# untitled.net
KiCad netlist of a schematic drawn in EAGLE
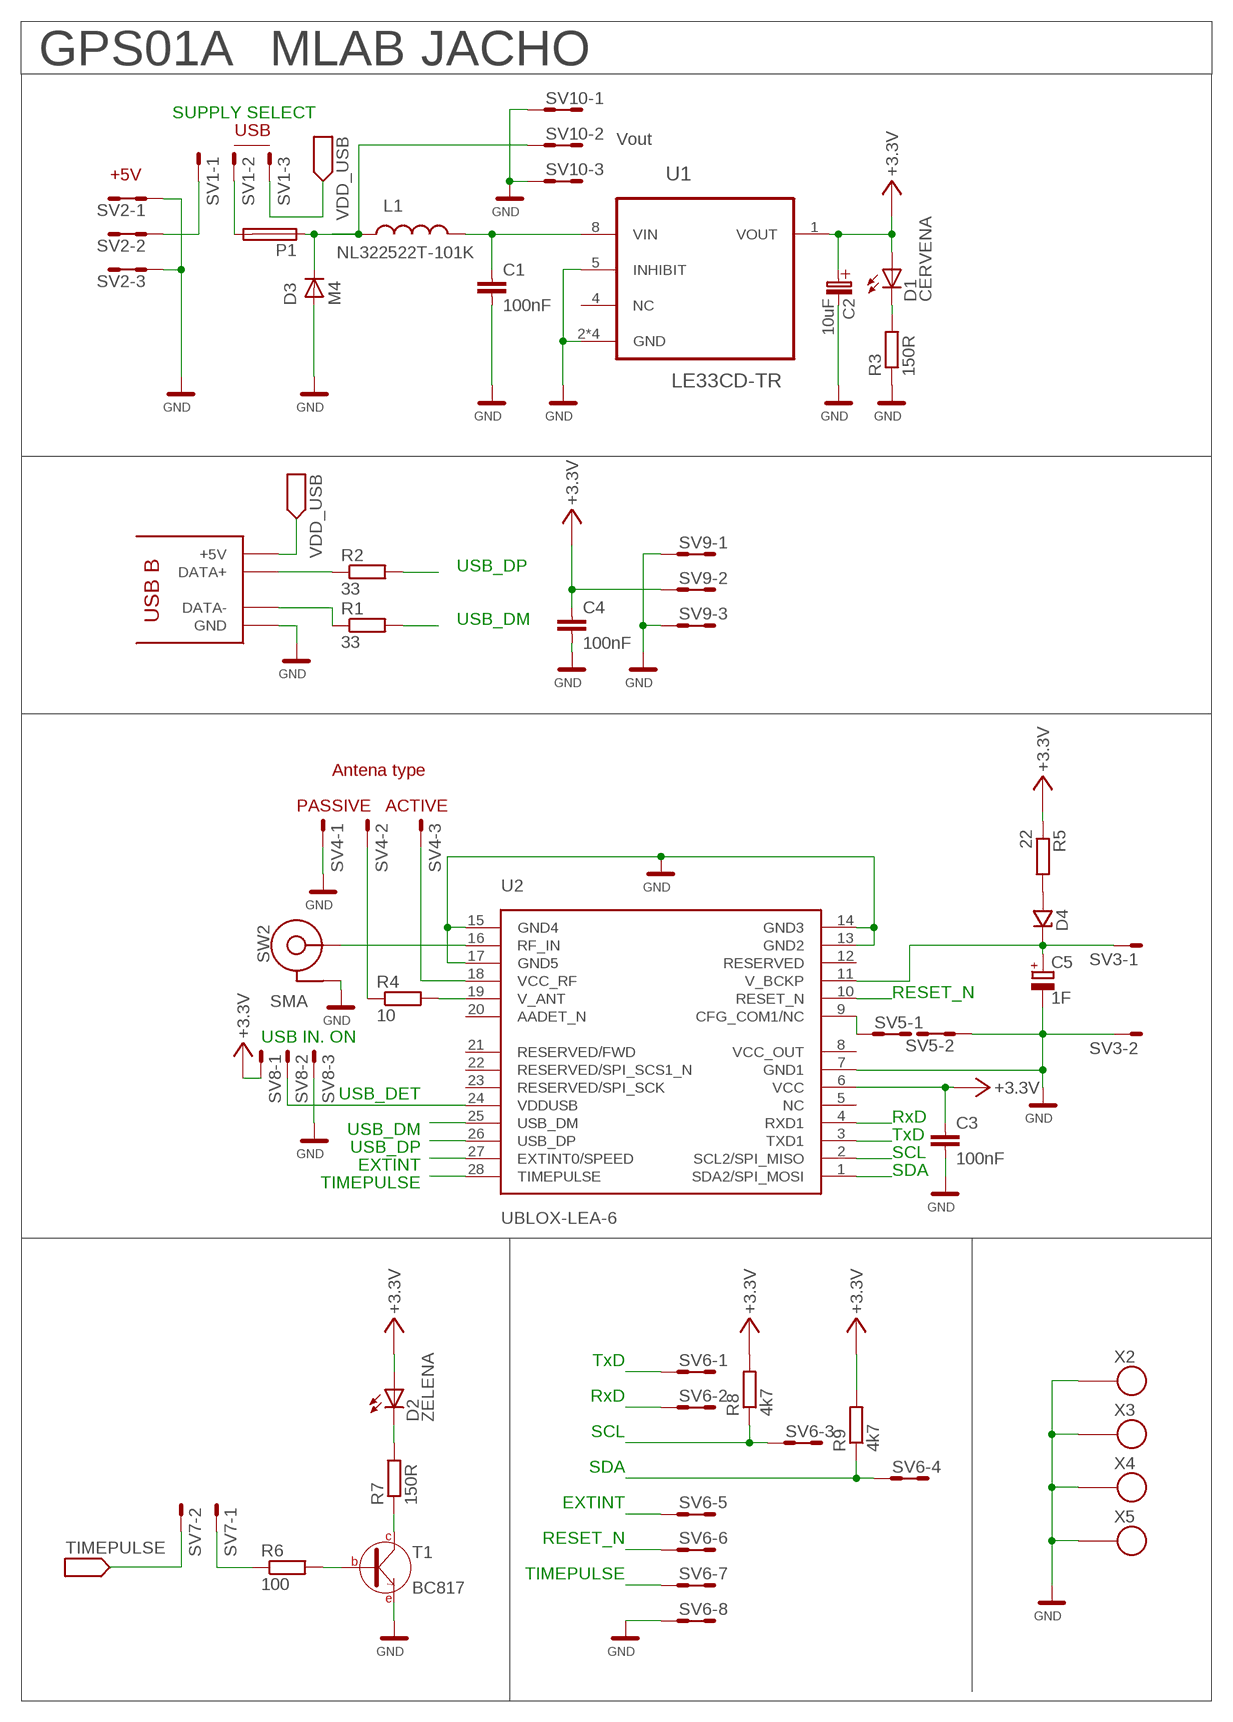
[diagram p0: schematic, sheet 1]

(export (version "E")
  (design (tool "Eeschema 10.0.6"))
  (components
    (comp (ref "C1")
      (value "100nF")
      (footprint "eagle-import:C0805")
      (libsource (lib "eagle-import") (part "C0805"))
    )
    (comp (ref "C2") (value "10uF") (footprint "eagle-import:B") (libsource (lib "eagle-import") (part "B")))
    (comp (ref "C3")
      (value "100nF")
      (footprint "eagle-import:C0805")
      (libsource (lib "eagle-import") (part "C0805"))
    )
    (comp (ref "C4")
      (value "100nF")
      (footprint "eagle-import:C0805")
      (libsource (lib "eagle-import") (part "C0805"))
    )
    (comp (ref "C5")
      (value "1F")
      (footprint "eagle-import:E3,5-8")
      (libsource (lib "eagle-import") (part "CPOL-EUE3.5-8"))
    )
    (comp (ref "D1")
      (value "CERVENA")
      (footprint "eagle-import:1206")
      (libsource (lib "eagle-import") (part "LED1206"))
    )
    (comp (ref "D2")
      (value "ZELENA")
      (footprint "eagle-import:1206")
      (libsource (lib "eagle-import") (part "LED1206"))
    )
    (comp (ref "D3")
      (value "M4")
      (footprint "eagle-import:SMA")
      (libsource (lib "eagle-import") (part "D-OB.SMA"))
    )
    (comp (ref "D4")
      (value "D-ZENEROVA")
      (footprint "eagle-import:MINIMELF")
      (libsource (lib "eagle-import") (part "D-ZENEROVA"))
    )
    (comp (ref "L1")
      (value "NL322522T-101K")
      (footprint "eagle-import:1210")
      (libsource (lib "eagle-import") (part "L1210"))
    )
    (comp (ref "P1")
      (value "POJISTKA_1812")
      (footprint "eagle-import:1812")
      (libsource (lib "eagle-import") (part "POJISTKA_1812"))
    )
    (comp (ref "R1")
      (value "33")
      (footprint "eagle-import:0805")
      (libsource (lib "eagle-import") (part "R0805"))
    )
    (comp (ref "R2")
      (value "33")
      (footprint "eagle-import:0805")
      (libsource (lib "eagle-import") (part "R0805"))
    )
    (comp (ref "R3")
      (value "150R")
      (footprint "eagle-import:0805")
      (libsource (lib "eagle-import") (part "R0805"))
    )
    (comp (ref "R4")
      (value "10")
      (footprint "eagle-import:0805")
      (libsource (lib "eagle-import") (part "R0805"))
    )
    (comp (ref "R5")
      (value "22")
      (footprint "eagle-import:0805")
      (libsource (lib "eagle-import") (part "R0805"))
    )
    (comp (ref "R6")
      (value "100")
      (footprint "eagle-import:0805")
      (libsource (lib "eagle-import") (part "R0805"))
    )
    (comp (ref "R7")
      (value "150R")
      (footprint "eagle-import:0805")
      (libsource (lib "eagle-import") (part "R0805"))
    )
    (comp (ref "R8")
      (value "4k7")
      (footprint "eagle-import:0805")
      (libsource (lib "eagle-import") (part "R0805"))
    )
    (comp (ref "R9")
      (value "4k7")
      (footprint "eagle-import:0805")
      (libsource (lib "eagle-import") (part "R0805"))
    )
    (comp (ref "SV1")
      (value "MA03-1")
      (footprint "eagle-import:MA03-1")
      (libsource (lib "eagle-import") (part "MA03-1"))
    )
    (comp (ref "SV2")
      (value "MA03-2")
      (footprint "eagle-import:MA03-2")
      (libsource (lib "eagle-import") (part "MA03-2"))
    )
    (comp (ref "SV3")
      (value "MA02-1")
      (footprint "eagle-import:MA02-1")
      (libsource (lib "eagle-import") (part "MA02-1"))
    )
    (comp (ref "SV4")
      (value "MA03-1")
      (footprint "eagle-import:MA03-1")
      (libsource (lib "eagle-import") (part "MA03-1"))
    )
    (comp (ref "SV5")
      (value "MA02-2")
      (footprint "eagle-import:MA02-2")
      (libsource (lib "eagle-import") (part "MA02-2"))
    )
    (comp (ref "SV6")
      (value "MA08-2")
      (footprint "eagle-import:MA08-2")
      (libsource (lib "eagle-import") (part "MA08-2"))
    )
    (comp (ref "SV7")
      (value "MA02-1")
      (footprint "eagle-import:MA02-1")
      (libsource (lib "eagle-import") (part "MA02-1"))
    )
    (comp (ref "SV8")
      (value "MA03-1")
      (footprint "eagle-import:MA03-1")
      (libsource (lib "eagle-import") (part "MA03-1"))
    )
    (comp (ref "SV9")
      (value "MA03-2")
      (footprint "eagle-import:MA03-2")
      (libsource (lib "eagle-import") (part "MA03-2"))
    )
    (comp (ref "SV10")
      (value "MA03-2")
      (footprint "eagle-import:MA03-2")
      (libsource (lib "eagle-import") (part "MA03-2"))
    )
    (comp (ref "SW2")
      (value "SMA")
      (footprint "eagle-import:SMA")
      (libsource (lib "eagle-import") (part "SMA"))
    )
    (comp (ref "T1")
      (value "BC817")
      (footprint "eagle-import:SOT23")
      (libsource (lib "eagle-import") (part "BC817"))
    )
    (comp (ref "U1")
      (value "LE33CD-TR")
      (footprint "eagle-import:SOIC127P600X175-8N")
      (libsource (lib "eagle-import") (part "LE33CD-TR"))
    )
    (comp (ref "U2")
      (value "UBLOX-LEA-6")
      (footprint "eagle-import:UBLOX-LEA-6")
      (libsource (lib "eagle-import") (part "UBLOX-LEA-6"))
    )
    (comp (ref "X1")
      (value "USB_B")
      (footprint "eagle-import:USB_B")
      (libsource (lib "eagle-import") (part "USB_B"))
    )
    (comp (ref "X2")
      (value "SROUB3M")
      (footprint "eagle-import:SROUB3M")
      (libsource (lib "eagle-import") (part "SROUB3M"))
    )
    (comp (ref "X3")
      (value "SROUB3M")
      (footprint "eagle-import:SROUB3M")
      (libsource (lib "eagle-import") (part "SROUB3M"))
    )
    (comp (ref "X4")
      (value "SROUB3M")
      (footprint "eagle-import:SROUB3M")
      (libsource (lib "eagle-import") (part "SROUB3M"))
    )
    (comp (ref "X5")
      (value "SROUB3M")
      (footprint "eagle-import:SROUB3M")
      (libsource (lib "eagle-import") (part "SROUB3M"))
    )
  )
  (nets
    (net (code "1") (name "+3.3V") (class "Default")
      (node (ref "C2") (pin "+") (pinfunction "C_EL+_+") (pintype "passive"))
      (node (ref "C3") (pin "1") (pinfunction "1_1") (pintype "passive"))
      (node (ref "C4") (pin "1") (pinfunction "1_1") (pintype "passive"))
      (node (ref "D1") (pin "A") (pinfunction "A_A") (pintype "passive"))
      (node (ref "D2") (pin "A") (pinfunction "A_A") (pintype "passive"))
      (node (ref "R5") (pin "1") (pinfunction "1_1") (pintype "passive"))
      (node (ref "R8") (pin "2") (pinfunction "2_2") (pintype "passive"))
      (node (ref "R9") (pin "2") (pinfunction "2_2") (pintype "passive"))
      (node (ref "SV8") (pin "1") (pinfunction "P$1_1") (pintype "passive"))
      (node (ref "SV9") (pin "3") (pinfunction "K_3") (pintype "passive"))
      (node (ref "SV9") (pin "4") (pinfunction "K_4") (pintype "passive"))
      (node (ref "U1") (pin "1") (pinfunction "VOUT_1") (pintype "output"))
      (node (ref "U2") (pin "6") (pinfunction "VCC_6") (pintype "bidirectional"))
    )
    (net (code "2") (name "/EXTINT") (class "Default")
      (node (ref "SV6") (pin "10") (pinfunction "K_10") (pintype "passive"))
      (node (ref "SV6") (pin "9") (pinfunction "K_9") (pintype "passive"))
      (node (ref "U2") (pin "27") (pinfunction "EXTINT0/SPEED_27") (pintype "bidirectional"))
    )
    (net (code "3") (name "/RESET_N") (class "Default")
      (node (ref "SV6") (pin "11") (pinfunction "K_11") (pintype "passive"))
      (node (ref "SV6") (pin "12") (pinfunction "K_12") (pintype "passive"))
      (node (ref "U2") (pin "10") (pinfunction "RESET_N_10") (pintype "bidirectional"))
    )
    (net (code "4") (name "/RXD") (class "Default")
      (node (ref "SV6") (pin "3") (pinfunction "K_3") (pintype "passive"))
      (node (ref "SV6") (pin "4") (pinfunction "K_4") (pintype "passive"))
      (node (ref "U2") (pin "4") (pinfunction "RXD1_4") (pintype "bidirectional"))
    )
    (net (code "5") (name "/SCL") (class "Default")
      (node (ref "R8") (pin "1") (pinfunction "1_1") (pintype "passive"))
      (node (ref "SV6") (pin "5") (pinfunction "K_5") (pintype "passive"))
      (node (ref "SV6") (pin "6") (pinfunction "K_6") (pintype "passive"))
      (node (ref "U2") (pin "2") (pinfunction "SCL2/SPI_MISO_2") (pintype "bidirectional"))
    )
    (net (code "6") (name "/SDA") (class "Default")
      (node (ref "R9") (pin "1") (pinfunction "1_1") (pintype "passive"))
      (node (ref "SV6") (pin "7") (pinfunction "K_7") (pintype "passive"))
      (node (ref "SV6") (pin "8") (pinfunction "K_8") (pintype "passive"))
      (node (ref "U2") (pin "1") (pinfunction "SDA2/SPI_MOSI_1") (pintype "bidirectional"))
    )
    (net (code "7") (name "/TIMEPULSE") (class "Default")
      (node (ref "SV6") (pin "13") (pinfunction "K_13") (pintype "passive"))
      (node (ref "SV6") (pin "14") (pinfunction "K_14") (pintype "passive"))
      (node (ref "SV7") (pin "2") (pinfunction "P$1_2") (pintype "passive"))
      (node (ref "U2") (pin "28") (pinfunction "TIMEPULSE_28") (pintype "bidirectional"))
    )
    (net (code "8") (name "/TXD") (class "Default")
      (node (ref "SV6") (pin "1") (pinfunction "K_1") (pintype "passive"))
      (node (ref "SV6") (pin "2") (pinfunction "K_2") (pintype "passive"))
      (node (ref "U2") (pin "3") (pinfunction "TXD1_3") (pintype "bidirectional"))
    )
    (net (code "9") (name "/USB_DM") (class "Default")
      (node (ref "R1") (pin "2") (pinfunction "2_2") (pintype "passive"))
      (node (ref "U2") (pin "25") (pinfunction "USB_DM_25") (pintype "bidirectional"))
    )
    (net (code "10") (name "/USB_DP") (class "Default")
      (node (ref "R2") (pin "2") (pinfunction "2_2") (pintype "passive"))
      (node (ref "U2") (pin "26") (pinfunction "USB_DP_26") (pintype "bidirectional"))
    )
    (net (code "11") (name "/VDD_USB") (class "Default")
      (node (ref "SV1") (pin "3") (pinfunction "P$1_3") (pintype "passive"))
      (node (ref "X1") (pin "1") (pinfunction "+5V_1") (pintype "bidirectional"))
    )
    (net (code "12") (name "GND") (class "Default")
      (node (ref "C1") (pin "2") (pinfunction "2_2") (pintype "passive"))
      (node (ref "C2") (pin "-") (pinfunction "C_EL-_-") (pintype "passive"))
      (node (ref "C3") (pin "2") (pinfunction "2_2") (pintype "passive"))
      (node (ref "C4") (pin "2") (pinfunction "2_2") (pintype "passive"))
      (node (ref "C5") (pin "-") (pinfunction "-_-") (pintype "passive"))
      (node (ref "D3") (pin "A") (pinfunction "A_A") (pintype "passive"))
      (node (ref "R3") (pin "1") (pinfunction "1_1") (pintype "passive"))
      (node (ref "SV10") (pin "1") (pinfunction "K_1") (pintype "passive"))
      (node (ref "SV10") (pin "2") (pinfunction "K_2") (pintype "passive"))
      (node (ref "SV10") (pin "5") (pinfunction "K_5") (pintype "passive"))
      (node (ref "SV10") (pin "6") (pinfunction "K_6") (pintype "passive"))
      (node (ref "SV2") (pin "1") (pinfunction "K_1") (pintype "passive"))
      (node (ref "SV2") (pin "2") (pinfunction "K_2") (pintype "passive"))
      (node (ref "SV2") (pin "5") (pinfunction "K_5") (pintype "passive"))
      (node (ref "SV2") (pin "6") (pinfunction "K_6") (pintype "passive"))
      (node (ref "SV3") (pin "2") (pinfunction "P$1_2") (pintype "passive"))
      (node (ref "SV4") (pin "1") (pinfunction "P$1_1") (pintype "passive"))
      (node (ref "SV5") (pin "3") (pinfunction "K_3") (pintype "passive"))
      (node (ref "SV5") (pin "4") (pinfunction "K_4") (pintype "passive"))
      (node (ref "SV6") (pin "15") (pinfunction "K_15") (pintype "passive"))
      (node (ref "SV6") (pin "16") (pinfunction "K_16") (pintype "passive"))
      (node (ref "SV8") (pin "3") (pinfunction "P$1_3") (pintype "passive"))
      (node (ref "SV9") (pin "1") (pinfunction "K_1") (pintype "passive"))
      (node (ref "SV9") (pin "2") (pinfunction "K_2") (pintype "passive"))
      (node (ref "SV9") (pin "5") (pinfunction "K_5") (pintype "passive"))
      (node (ref "SV9") (pin "6") (pinfunction "K_6") (pintype "passive"))
      (node (ref "SW2") (pin "-1") (pinfunction "-_-1") (pintype "passive"))
      (node (ref "SW2") (pin "-2") (pinfunction "-_-2") (pintype "passive"))
      (node (ref "SW2") (pin "-3") (pinfunction "-_-3") (pintype "passive"))
      (node (ref "SW2") (pin "-4") (pinfunction "-_-4") (pintype "passive"))
      (node (ref "T1") (pin "2") (pinfunction "E_2") (pintype "passive"))
      (node (ref "U1") (pin "2") (pinfunction "GND_2") (pintype "passive"))
      (node (ref "U1") (pin "3") (pinfunction "GND_3") (pintype "passive"))
      (node (ref "U1") (pin "5") (pinfunction "INHIBIT_5") (pintype "passive"))
      (node (ref "U1") (pin "6") (pinfunction "GND_6") (pintype "passive"))
      (node (ref "U1") (pin "7") (pinfunction "GND_7") (pintype "passive"))
      (node (ref "U2") (pin "13") (pinfunction "GND2_13") (pintype "bidirectional"))
      (node (ref "U2") (pin "14") (pinfunction "GND3_14") (pintype "bidirectional"))
      (node (ref "U2") (pin "15") (pinfunction "GND4_15") (pintype "bidirectional"))
      (node (ref "U2") (pin "17") (pinfunction "GND5_17") (pintype "bidirectional"))
      (node (ref "U2") (pin "7") (pinfunction "GND1_7") (pintype "bidirectional"))
      (node (ref "X1") (pin "4") (pinfunction "GND_4") (pintype "bidirectional"))
      (node (ref "X1") (pin "GND") (pinfunction "GND_GND") (pintype "bidirectional"))
      (node (ref "X1") (pin "GND2") (pinfunction "GND_GND2") (pintype "bidirectional"))
      (node (ref "X2") (pin "P$1") (pinfunction "P$1_P$1") (pintype "bidirectional"))
      (node (ref "X3") (pin "P$1") (pinfunction "P$1_P$1") (pintype "bidirectional"))
      (node (ref "X4") (pin "P$1") (pinfunction "P$1_P$1") (pintype "bidirectional"))
      (node (ref "X5") (pin "P$1") (pinfunction "P$1_P$1") (pintype "bidirectional"))
    )
    (net (code "13") (name "Net-(D1-C)") (class "Default")
      (node (ref "D1") (pin "K") (pinfunction "C_K") (pintype "passive"))
      (node (ref "R3") (pin "2") (pinfunction "2_2") (pintype "passive"))
    )
    (net (code "14") (name "Net-(D2-C)") (class "Default")
      (node (ref "D2") (pin "K") (pinfunction "C_K") (pintype "passive"))
      (node (ref "R7") (pin "2") (pinfunction "2_2") (pintype "passive"))
    )
    (net (code "15") (name "Net-(D3-C)") (class "Default")
      (node (ref "D3") (pin "K") (pinfunction "C_K") (pintype "passive"))
      (node (ref "L1") (pin "P$1") (pinfunction "1_P$1") (pintype "passive"))
      (node (ref "P1") (pin "1") (pinfunction "1_1") (pintype "passive"))
      (node (ref "SV10") (pin "3") (pinfunction "K_3") (pintype "passive"))
      (node (ref "SV10") (pin "4") (pinfunction "K_4") (pintype "passive"))
    )
    (net (code "16") (name "Net-(D4-K)") (class "Default")
      (node (ref "C5") (pin "+") (pinfunction "+_+") (pintype "passive"))
      (node (ref "D4") (pin "C") (pinfunction "K_C") (pintype "passive"))
      (node (ref "SV3") (pin "1") (pinfunction "P$1_1") (pintype "passive"))
      (node (ref "U2") (pin "11") (pinfunction "V_BCKP_11") (pintype "bidirectional"))
    )
    (net (code "17") (name "Net-(D4-PadA)") (class "Default")
      (node (ref "D4") (pin "A") (pinfunction "A_A") (pintype "passive"))
      (node (ref "R5") (pin "2") (pinfunction "2_2") (pintype "passive"))
    )
    (net (code "18") (name "Net-(L1-2)") (class "Default")
      (node (ref "C1") (pin "1") (pinfunction "1_1") (pintype "passive"))
      (node (ref "L1") (pin "P$2") (pinfunction "2_P$2") (pintype "passive"))
      (node (ref "U1") (pin "8") (pinfunction "VIN_8") (pintype "power_in"))
    )
    (net (code "19") (name "Net-(SV1A-P$1)") (class "Default")
      (node (ref "SV1") (pin "1") (pinfunction "P$1_1") (pintype "passive"))
      (node (ref "SV2") (pin "3") (pinfunction "K_3") (pintype "passive"))
      (node (ref "SV2") (pin "4") (pinfunction "K_4") (pintype "passive"))
    )
    (net (code "20") (name "Net-(SV1B-P$1)") (class "Default")
      (node (ref "P1") (pin "2") (pinfunction "2_2") (pintype "passive"))
      (node (ref "SV1") (pin "2") (pinfunction "P$1_2") (pintype "passive"))
    )
    (net (code "21") (name "Net-(SV4B-P$1)") (class "Default")
      (node (ref "R4") (pin "1") (pinfunction "1_1") (pintype "passive"))
      (node (ref "SV4") (pin "2") (pinfunction "P$1_2") (pintype "passive"))
    )
    (net (code "22") (name "Net-(SV4C-P$1)") (class "Default")
      (node (ref "SV4") (pin "3") (pinfunction "P$1_3") (pintype "passive"))
      (node (ref "U2") (pin "18") (pinfunction "VCC_RF_18") (pintype "bidirectional"))
    )
    (net (code "23") (name "Net-(SV7A-P$1)") (class "Default")
      (node (ref "R6") (pin "1") (pinfunction "1_1") (pintype "passive"))
      (node (ref "SV7") (pin "1") (pinfunction "P$1_1") (pintype "passive"))
    )
    (net (code "24") (name "Net-(SV8B-P$1)") (class "Default")
      (node (ref "SV8") (pin "2") (pinfunction "P$1_2") (pintype "passive"))
      (node (ref "U2") (pin "24") (pinfunction "VDDUSB_24") (pintype "bidirectional"))
    )
    (net (code "25") (name "Net-(T1-B)") (class "Default")
      (node (ref "R6") (pin "2") (pinfunction "2_2") (pintype "passive"))
      (node (ref "T1") (pin "1") (pinfunction "B_1") (pintype "passive"))
    )
    (net (code "26") (name "Net-(T1-C)") (class "Default")
      (node (ref "R7") (pin "1") (pinfunction "1_1") (pintype "passive"))
      (node (ref "T1") (pin "3") (pinfunction "C_3") (pintype "passive"))
    )
    (net (code "27") (name "Net-(U2-CFG_COM1{slash}NC)") (class "Default")
      (node (ref "SV5") (pin "1") (pinfunction "K_1") (pintype "passive"))
      (node (ref "SV5") (pin "2") (pinfunction "K_2") (pintype "passive"))
      (node (ref "U2") (pin "9") (pinfunction "CFG_COM1/NC_9") (pintype "bidirectional"))
    )
    (net (code "28") (name "Net-(U2-RF_IN)") (class "Default")
      (node (ref "SW2") (pin "+") (pinfunction "+_+") (pintype "passive"))
      (node (ref "U2") (pin "16") (pinfunction "RF_IN_16") (pintype "bidirectional"))
    )
    (net (code "29") (name "Net-(U2-V_ANT)") (class "Default")
      (node (ref "R4") (pin "2") (pinfunction "2_2") (pintype "passive"))
      (node (ref "U2") (pin "19") (pinfunction "V_ANT_19") (pintype "bidirectional"))
    )
    (net (code "30") (name "Net-(X1-DATA+)") (class "Default")
      (node (ref "R2") (pin "1") (pinfunction "1_1") (pintype "passive"))
      (node (ref "X1") (pin "3") (pinfunction "DATA+_3") (pintype "bidirectional"))
    )
    (net (code "31") (name "Net-(X1-DATA-)") (class "Default")
      (node (ref "R1") (pin "1") (pinfunction "1_1") (pintype "passive"))
      (node (ref "X1") (pin "2") (pinfunction "DATA-_2") (pintype "bidirectional"))
    )
    (net (code "32") (name "unconnected-(U1-NC-Pad4)") (class "Default")
      (node (ref "U1") (pin "4") (pinfunction "NC_4") (pintype "no_connect"))
    )
    (net (code "33") (name "unconnected-(U2-AADET_N-Pad20)") (class "Default")
      (node (ref "U2") (pin "20") (pinfunction "AADET_N_20") (pintype "bidirectional"))
    )
    (net (code "34") (name "unconnected-(U2-NC-Pad5)") (class "Default")
      (node (ref "U2") (pin "5") (pinfunction "NC_5") (pintype "bidirectional"))
    )
    (net (code "35") (name "unconnected-(U2-RESERVED-Pad12)") (class "Default")
      (node (ref "U2") (pin "12") (pinfunction "RESERVED_12") (pintype "bidirectional"))
    )
    (net (code "36") (name "unconnected-(U2-RESERVED{slash}FWD-Pad21)") (class "Default")
      (node (ref "U2") (pin "21") (pinfunction "RESERVED/FWD_21") (pintype "bidirectional"))
    )
    (net (code "37") (name "unconnected-(U2-RESERVED{slash}SPI_SCK-Pad23)") (class "Default")
      (node (ref "U2") (pin "23") (pinfunction "RESERVED/SPI_SCK_23") (pintype "bidirectional"))
    )
    (net (code "38") (name "unconnected-(U2-RESERVED{slash}SPI_SCS1_N-Pad22)") (class "Default")
      (node (ref "U2") (pin "22") (pinfunction "RESERVED/SPI_SCS1_N_22") (pintype "bidirectional"))
    )
    (net (code "39") (name "unconnected-(U2-VCC_OUT-Pad8)") (class "Default")
      (node (ref "U2") (pin "8") (pinfunction "VCC_OUT_8") (pintype "bidirectional"))
    )
  )
)
